# communication_module.net
KiCad netlist of a schematic drawn in EAGLE
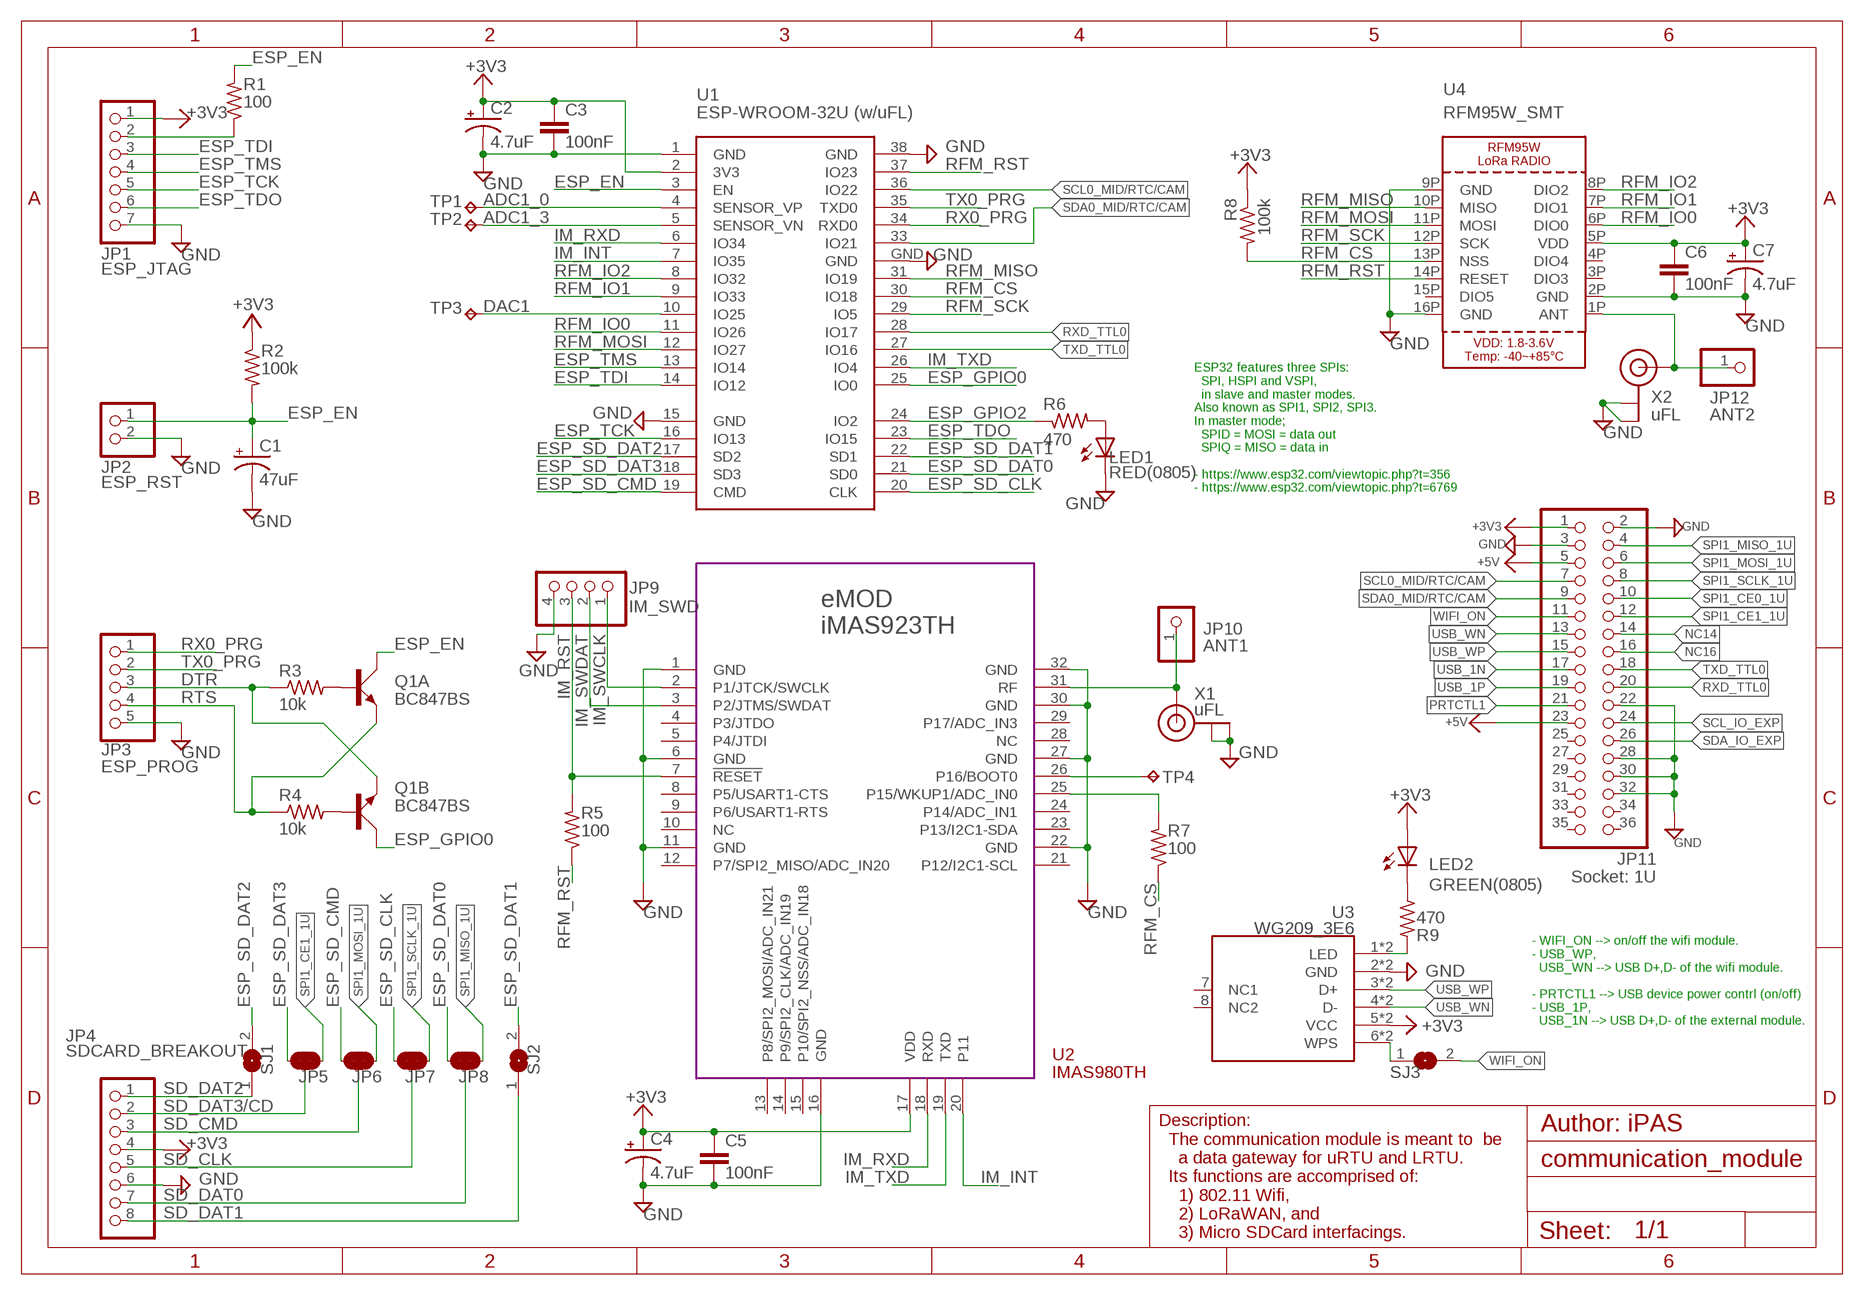
[diagram p0: schematic, sheet 1]

(export (version "E")
  (design (tool "Eeschema 10.0.6"))
  (components
    (comp (ref "C1")
      (value "47uF")
      (footprint "eagle-import:RCL_150CLZ-1014")
      (libsource (lib "eagle-import") (part "RCL_CPOL-US150CLZ-1014"))
    )
    (comp (ref "C2")
      (value "4.7uF")
      (footprint "eagle-import:RCL_150CLZ-1014")
      (libsource (lib "eagle-import") (part "RCL_CPOL-US150CLZ-1014"))
    )
    (comp (ref "C3")
      (value "100nF")
      (footprint "eagle-import:RCL_C1206")
      (libsource (lib "eagle-import") (part "RCL_C-EUC1206"))
    )
    (comp (ref "C4")
      (value "4.7uF")
      (footprint "eagle-import:RCL_150CLZ-1014")
      (libsource (lib "eagle-import") (part "RCL_CPOL-US150CLZ-1014"))
    )
    (comp (ref "C5")
      (value "100nF")
      (footprint "eagle-import:RCL_C1206")
      (libsource (lib "eagle-import") (part "RCL_C-EUC1206"))
    )
    (comp (ref "C6")
      (value "100nF")
      (footprint "eagle-import:RCL_C1206")
      (libsource (lib "eagle-import") (part "RCL_C-EUC1206"))
    )
    (comp (ref "C7")
      (value "4.7uF")
      (footprint "eagle-import:RCL_150CLZ-1014")
      (libsource (lib "eagle-import") (part "RCL_CPOL-US150CLZ-1014"))
    )
    (comp (ref "JP1")
      (value "ESP_JTAG")
      (footprint "eagle-import:1X07")
      (libsource (lib "eagle-import") (part "PINHD-1X7"))
    )
    (comp (ref "JP2")
      (value "ESP_RST")
      (footprint "eagle-import:1X02")
      (libsource (lib "eagle-import") (part "PINHD-1X2"))
    )
    (comp (ref "JP3")
      (value "ESP_PROG")
      (footprint "eagle-import:1X05")
      (libsource (lib "eagle-import") (part "PINHD-1X5"))
    )
    (comp (ref "JP4")
      (value "SDCARD_BREAKOUT")
      (footprint "eagle-import:1X08")
      (libsource (lib "eagle-import") (part "PINHD-1X8"))
    )
    (comp (ref "JP5")
      (value "JUMPER-SMT_3_NO_NO-SILK")
      (footprint "eagle-import:SMT-JUMPER_3_NO_NO-SILK")
      (libsource (lib "eagle-import") (part "JUMPER-SMT_3_NO_NO-SILK"))
    )
    (comp (ref "JP6")
      (value "JUMPER-SMT_3_NO_NO-SILK")
      (footprint "eagle-import:SMT-JUMPER_3_NO_NO-SILK")
      (libsource (lib "eagle-import") (part "JUMPER-SMT_3_NO_NO-SILK"))
    )
    (comp (ref "JP7")
      (value "JUMPER-SMT_3_NO_NO-SILK")
      (footprint "eagle-import:SMT-JUMPER_3_NO_NO-SILK")
      (libsource (lib "eagle-import") (part "JUMPER-SMT_3_NO_NO-SILK"))
    )
    (comp (ref "JP8")
      (value "JUMPER-SMT_3_NO_NO-SILK")
      (footprint "eagle-import:SMT-JUMPER_3_NO_NO-SILK")
      (libsource (lib "eagle-import") (part "JUMPER-SMT_3_NO_NO-SILK"))
    )
    (comp (ref "JP9")
      (value "IM_SWD")
      (footprint "eagle-import:1X04")
      (libsource (lib "eagle-import") (part "PINHD-1X4"))
    )
    (comp (ref "JP10")
      (value "ANT1")
      (footprint "eagle-import:1X01_ROUND")
      (libsource (lib "eagle-import") (part "HEADER-1X1ROUND"))
    )
    (comp (ref "JP11")
      (value "Socket: 1U")
      (footprint "eagle-import:2X18")
      (libsource (lib "eagle-import") (part "PINHD-2X18"))
    )
    (comp (ref "JP12")
      (value "ANT2")
      (footprint "eagle-import:1X01_ROUND")
      (libsource (lib "eagle-import") (part "HEADER-1X1ROUND"))
    )
    (comp (ref "LED1")
      (value "RED(0805)")
      (footprint "eagle-import:CHIP-LED0805")
      (libsource (lib "eagle-import") (part "LEDCHIP-LED0805"))
    )
    (comp (ref "LED2")
      (value "GREEN(0805)")
      (footprint "eagle-import:CHIP-LED0805")
      (libsource (lib "eagle-import") (part "LEDCHIP-LED0805"))
    )
    (comp (ref "Q1")
      (value "BC847BS")
      (footprint "eagle-import:SOT363_PHILIPS")
      (libsource (lib "eagle-import") (part "BC847BS"))
    )
    (comp (ref "R1")
      (value "100")
      (footprint "eagle-import:RCL_M0805")
      (libsource (lib "eagle-import") (part "RCL_R-USM0805"))
    )
    (comp (ref "R2")
      (value "100k")
      (footprint "eagle-import:RCL_M0805")
      (libsource (lib "eagle-import") (part "RCL_R-USM0805"))
    )
    (comp (ref "R3")
      (value "10k")
      (footprint "eagle-import:RCL_M0805")
      (libsource (lib "eagle-import") (part "RCL_R-USM0805"))
    )
    (comp (ref "R4")
      (value "10k")
      (footprint "eagle-import:RCL_M0805")
      (libsource (lib "eagle-import") (part "RCL_R-USM0805"))
    )
    (comp (ref "R5")
      (value "100")
      (footprint "eagle-import:RCL_M0805")
      (libsource (lib "eagle-import") (part "RCL_R-USM0805"))
    )
    (comp (ref "R6")
      (value "470")
      (footprint "eagle-import:RCL_M0805")
      (libsource (lib "eagle-import") (part "RCL_R-USM0805"))
    )
    (comp (ref "R7")
      (value "100")
      (footprint "eagle-import:RCL_M0805")
      (libsource (lib "eagle-import") (part "RCL_R-USM0805"))
    )
    (comp (ref "R8")
      (value "100k")
      (footprint "eagle-import:RCL_M0805")
      (libsource (lib "eagle-import") (part "RCL_R-USM0805"))
    )
    (comp (ref "R9")
      (value "470")
      (footprint "eagle-import:RCL_M0805")
      (libsource (lib "eagle-import") (part "RCL_R-USM0805"))
    )
    (comp (ref "SJ1")
      (value "SOLDERJUMPERREFLOW")
      (footprint "eagle-import:SOLDERJUMPER_REFLOW")
      (libsource (lib "eagle-import") (part "SOLDERJUMPERREFLOW"))
    )
    (comp (ref "SJ2")
      (value "SOLDERJUMPERREFLOW")
      (footprint "eagle-import:SOLDERJUMPER_REFLOW")
      (libsource (lib "eagle-import") (part "SOLDERJUMPERREFLOW"))
    )
    (comp (ref "SJ3")
      (value "SOLDERJUMPERREFLOW")
      (footprint "eagle-import:SOLDERJUMPER_REFLOW")
      (libsource (lib "eagle-import") (part "SOLDERJUMPERREFLOW"))
    )
    (comp (ref "TP1")
      (value "TPB1,27")
      (footprint "eagle-import:B1,27")
      (libsource (lib "eagle-import") (part "TPB1,27"))
    )
    (comp (ref "TP2")
      (value "TPB1,27")
      (footprint "eagle-import:B1,27")
      (libsource (lib "eagle-import") (part "TPB1,27"))
    )
    (comp (ref "TP3")
      (value "TPB1,27")
      (footprint "eagle-import:B1,27")
      (libsource (lib "eagle-import") (part "TPB1,27"))
    )
    (comp (ref "TP4")
      (value "TPB1,27")
      (footprint "eagle-import:B1,27")
      (libsource (lib "eagle-import") (part "TPB1,27"))
    )
    (comp (ref "U1")
      (value "ESP-WROOM-32U (w/uFL)")
      (footprint "eagle-import:ESP-WROOM-32")
      (libsource (lib "eagle-import") (part "ESP-WROOM-32"))
    )
    (comp (ref "U2")
      (value "IMAS980TH")
      (footprint "eagle-import:IMAS923TH")
      (libsource (lib "eagle-import") (part "IMAS980TH"))
    )
    (comp (ref "U3")
      (value "WG209_3E6")
      (footprint "eagle-import:WG209")
      (libsource (lib "eagle-import") (part "WG209"))
    )
    (comp (ref "U4")
      (value "RFM95W_SMT")
      (footprint "eagle-import:RFMHCW_SMT")
      (libsource (lib "eagle-import") (part "RFM95W_SMT"))
    )
    (comp (ref "X1")
      (value "uFL")
      (footprint "eagle-import:U.FL")
      (libsource (lib "eagle-import") (part "ANTENNA_U.FL"))
    )
    (comp (ref "X2")
      (value "uFL")
      (footprint "eagle-import:U.FL")
      (libsource (lib "eagle-import") (part "ANTENNA_U.FL"))
    )
  )
  (nets
    (net (code "1") (name "+3V3") (class "Default")
      (node (ref "C2") (pin "+") (pinfunction "+_+") (pintype "passive"))
      (node (ref "C3") (pin "1") (pinfunction "1_1") (pintype "passive"))
      (node (ref "C4") (pin "+") (pinfunction "+_+") (pintype "passive"))
      (node (ref "C5") (pin "1") (pinfunction "1_1") (pintype "passive"))
      (node (ref "C6") (pin "1") (pinfunction "1_1") (pintype "passive"))
      (node (ref "C7") (pin "+") (pinfunction "+_+") (pintype "passive"))
      (node (ref "JP1") (pin "1") (pinfunction "1_1") (pintype "passive"))
      (node (ref "JP11") (pin "1") (pinfunction "1_1") (pintype "passive"))
      (node (ref "JP4") (pin "4") (pinfunction "4_4") (pintype "passive"))
      (node (ref "LED2") (pin "A") (pinfunction "A_A") (pintype "passive"))
      (node (ref "R2") (pin "1") (pinfunction "1_1") (pintype "passive"))
      (node (ref "R8") (pin "1") (pinfunction "1_1") (pintype "passive"))
      (node (ref "U1") (pin "2") (pinfunction "3V3_2") (pintype "power_in"))
      (node (ref "U2") (pin "17") (pinfunction "VDD_17") (pintype "power_in"))
      (node (ref "U3") (pin "5") (pinfunction "VCC_5") (pintype "power_in"))
      (node (ref "U3") (pin "5P") (pinfunction "VCC_5P") (pintype "power_in"))
      (node (ref "U4") (pin "5P") (pinfunction "VDD_5P") (pintype "power_in"))
    )
    (net (code "2") (name "+5V") (class "Default")
      (node (ref "JP11") (pin "23") (pinfunction "23_23") (pintype "passive"))
      (node (ref "JP11") (pin "5") (pinfunction "5_5") (pintype "passive"))
    )
    (net (code "3") (name "/ADC1_0") (class "Default")
      (node (ref "TP1") (pin "TP") (pinfunction "TP_TP") (pintype "input"))
      (node (ref "U1") (pin "4") (pinfunction "SENSOR_VP_4") (pintype "bidirectional"))
    )
    (net (code "4") (name "/ADC1_3") (class "Default")
      (node (ref "TP2") (pin "TP") (pinfunction "TP_TP") (pintype "input"))
      (node (ref "U1") (pin "5") (pinfunction "SENSOR_VN_5") (pintype "bidirectional"))
    )
    (net (code "5") (name "/DAC1") (class "Default")
      (node (ref "TP3") (pin "TP") (pinfunction "TP_TP") (pintype "input"))
      (node (ref "U1") (pin "10") (pinfunction "IO25_10") (pintype "bidirectional"))
    )
    (net (code "6") (name "/DTR") (class "Default")
      (node (ref "JP3") (pin "3") (pinfunction "3_3") (pintype "passive"))
      (node (ref "Q1") (pin "4") (pinfunction "E_4") (pintype "passive"))
      (node (ref "R3") (pin "1") (pinfunction "1_1") (pintype "passive"))
    )
    (net (code "7") (name "/ESP_EN") (class "Default")
      (node (ref "C1") (pin "+") (pinfunction "+_+") (pintype "passive"))
      (node (ref "JP2") (pin "1") (pinfunction "1_1") (pintype "passive"))
      (node (ref "Q1") (pin "6") (pinfunction "C_6") (pintype "passive"))
      (node (ref "R1") (pin "2") (pinfunction "2_2") (pintype "passive"))
      (node (ref "R2") (pin "2") (pinfunction "2_2") (pintype "passive"))
      (node (ref "U1") (pin "3") (pinfunction "EN_3") (pintype "input"))
    )
    (net (code "8") (name "/ESP_GPIO0") (class "Default")
      (node (ref "Q1") (pin "3") (pinfunction "C_3") (pintype "passive"))
      (node (ref "U1") (pin "25") (pinfunction "IO0_25") (pintype "bidirectional"))
    )
    (net (code "9") (name "/ESP_GPIO2") (class "Default")
      (node (ref "R6") (pin "1") (pinfunction "1_1") (pintype "passive"))
      (node (ref "U1") (pin "24") (pinfunction "IO2_24") (pintype "bidirectional"))
    )
    (net (code "10") (name "/ESP_SD_CLK") (class "Default")
      (node (ref "JP7") (pin "1") (pinfunction "1_1") (pintype "passive"))
      (node (ref "U1") (pin "20") (pinfunction "CLK_20") (pintype "bidirectional"))
    )
    (net (code "11") (name "/ESP_SD_CMD") (class "Default")
      (node (ref "JP6") (pin "1") (pinfunction "1_1") (pintype "passive"))
      (node (ref "U1") (pin "19") (pinfunction "CMD_19") (pintype "bidirectional"))
    )
    (net (code "12") (name "/ESP_SD_DAT0") (class "Default")
      (node (ref "JP8") (pin "1") (pinfunction "1_1") (pintype "passive"))
      (node (ref "U1") (pin "21") (pinfunction "SD0_21") (pintype "bidirectional"))
    )
    (net (code "13") (name "/ESP_SD_DAT1") (class "Default")
      (node (ref "SJ2") (pin "2") (pinfunction "2_2") (pintype "passive"))
      (node (ref "U1") (pin "22") (pinfunction "SD1_22") (pintype "bidirectional"))
    )
    (net (code "14") (name "/ESP_SD_DAT2") (class "Default")
      (node (ref "SJ1") (pin "2") (pinfunction "2_2") (pintype "passive"))
      (node (ref "U1") (pin "17") (pinfunction "SD2_17") (pintype "bidirectional"))
    )
    (net (code "15") (name "/ESP_SD_DAT3") (class "Default")
      (node (ref "JP5") (pin "1") (pinfunction "1_1") (pintype "passive"))
      (node (ref "U1") (pin "18") (pinfunction "SD3_18") (pintype "bidirectional"))
    )
    (net (code "16") (name "/ESP_TCK") (class "Default")
      (node (ref "JP1") (pin "5") (pinfunction "5_5") (pintype "passive"))
      (node (ref "U1") (pin "16") (pinfunction "IO13_16") (pintype "bidirectional"))
    )
    (net (code "17") (name "/ESP_TDI") (class "Default")
      (node (ref "JP1") (pin "3") (pinfunction "3_3") (pintype "passive"))
      (node (ref "U1") (pin "14") (pinfunction "IO12_14") (pintype "bidirectional"))
    )
    (net (code "18") (name "/ESP_TDO") (class "Default")
      (node (ref "JP1") (pin "6") (pinfunction "6_6") (pintype "passive"))
      (node (ref "U1") (pin "23") (pinfunction "IO15_23") (pintype "bidirectional"))
    )
    (net (code "19") (name "/ESP_TMS") (class "Default")
      (node (ref "JP1") (pin "4") (pinfunction "4_4") (pintype "passive"))
      (node (ref "U1") (pin "13") (pinfunction "IO14_13") (pintype "bidirectional"))
    )
    (net (code "20") (name "/IM_INT") (class "Default")
      (node (ref "U1") (pin "7") (pinfunction "IO35_7") (pintype "bidirectional"))
      (node (ref "U2") (pin "20") (pinfunction "P11_20") (pintype "bidirectional"))
    )
    (net (code "21") (name "/IM_RST") (class "Default")
      (node (ref "JP9") (pin "3") (pinfunction "3_3") (pintype "passive"))
      (node (ref "R5") (pin "2") (pinfunction "2_2") (pintype "passive"))
      (node (ref "U2") (pin "7") (pinfunction "~{RESET}_7") (pintype "passive"))
    )
    (net (code "22") (name "/IM_RXD") (class "Default")
      (node (ref "U1") (pin "6") (pinfunction "IO34_6") (pintype "bidirectional"))
      (node (ref "U2") (pin "18") (pinfunction "RXD_18") (pintype "bidirectional"))
    )
    (net (code "23") (name "/IM_SWCLK") (class "Default")
      (node (ref "JP9") (pin "1") (pinfunction "1_1") (pintype "passive"))
      (node (ref "U2") (pin "2") (pinfunction "P1/JTCK/SWCLK_2") (pintype "bidirectional"))
    )
    (net (code "24") (name "/IM_SWDAT") (class "Default")
      (node (ref "JP9") (pin "2") (pinfunction "2_2") (pintype "passive"))
      (node (ref "U2") (pin "3") (pinfunction "P2/JTMS/SWDAT_3") (pintype "bidirectional"))
    )
    (net (code "25") (name "/IM_TXD") (class "Default")
      (node (ref "U1") (pin "26") (pinfunction "IO4_26") (pintype "bidirectional"))
      (node (ref "U2") (pin "19") (pinfunction "TXD_19") (pintype "bidirectional"))
    )
    (net (code "26") (name "/RFM_CS") (class "Default")
      (node (ref "R7") (pin "1") (pinfunction "1_1") (pintype "passive"))
      (node (ref "R8") (pin "2") (pinfunction "2_2") (pintype "passive"))
      (node (ref "U1") (pin "30") (pinfunction "IO18_30") (pintype "bidirectional"))
      (node (ref "U4") (pin "13P") (pinfunction "NSS_13P") (pintype "input"))
    )
    (net (code "27") (name "/RFM_IO0") (class "Default")
      (node (ref "U1") (pin "11") (pinfunction "IO26_11") (pintype "bidirectional"))
      (node (ref "U4") (pin "6P") (pinfunction "DIO0_6P") (pintype "bidirectional"))
    )
    (net (code "28") (name "/RFM_IO1") (class "Default")
      (node (ref "U1") (pin "9") (pinfunction "IO33_9") (pintype "bidirectional"))
      (node (ref "U4") (pin "7P") (pinfunction "DIO1_7P") (pintype "bidirectional"))
    )
    (net (code "29") (name "/RFM_IO2") (class "Default")
      (node (ref "U1") (pin "8") (pinfunction "IO32_8") (pintype "bidirectional"))
      (node (ref "U4") (pin "8P") (pinfunction "DIO2_8P") (pintype "bidirectional"))
    )
    (net (code "30") (name "/RFM_MISO") (class "Default")
      (node (ref "U1") (pin "31") (pinfunction "IO19_31") (pintype "bidirectional"))
      (node (ref "U4") (pin "10P") (pinfunction "MISO_10P") (pintype "output"))
    )
    (net (code "31") (name "/RFM_MOSI") (class "Default")
      (node (ref "U1") (pin "12") (pinfunction "IO27_12") (pintype "bidirectional"))
      (node (ref "U4") (pin "11P") (pinfunction "MOSI_11P") (pintype "input"))
    )
    (net (code "32") (name "/RFM_RST") (class "Default")
      (node (ref "R5") (pin "1") (pinfunction "1_1") (pintype "passive"))
      (node (ref "U1") (pin "37") (pinfunction "IO23_37") (pintype "bidirectional"))
      (node (ref "U4") (pin "14P") (pinfunction "RESET_14P") (pintype "input"))
    )
    (net (code "33") (name "/RFM_SCK") (class "Default")
      (node (ref "U1") (pin "29") (pinfunction "IO5_29") (pintype "bidirectional"))
      (node (ref "U4") (pin "12P") (pinfunction "SCK_12P") (pintype "input"))
    )
    (net (code "34") (name "/RTS") (class "Default")
      (node (ref "JP3") (pin "4") (pinfunction "4_4") (pintype "passive"))
      (node (ref "Q1") (pin "1") (pinfunction "E_1") (pintype "passive"))
      (node (ref "R4") (pin "1") (pinfunction "1_1") (pintype "passive"))
    )
    (net (code "35") (name "/RX0_PRG") (class "Default")
      (node (ref "JP3") (pin "1") (pinfunction "1_1") (pintype "passive"))
      (node (ref "U1") (pin "34") (pinfunction "RXD0_34") (pintype "bidirectional"))
    )
    (net (code "36") (name "/SD_CLK") (class "Default")
      (node (ref "JP4") (pin "5") (pinfunction "5_5") (pintype "passive"))
      (node (ref "JP7") (pin "2") (pinfunction "2_2") (pintype "passive"))
    )
    (net (code "37") (name "/SD_CMD") (class "Default")
      (node (ref "JP4") (pin "3") (pinfunction "3_3") (pintype "passive"))
      (node (ref "JP6") (pin "2") (pinfunction "2_2") (pintype "passive"))
    )
    (net (code "38") (name "/SD_DAT0") (class "Default")
      (node (ref "JP4") (pin "7") (pinfunction "7_7") (pintype "passive"))
      (node (ref "JP8") (pin "2") (pinfunction "2_2") (pintype "passive"))
    )
    (net (code "39") (name "/SD_DAT1") (class "Default")
      (node (ref "JP4") (pin "8") (pinfunction "8_8") (pintype "passive"))
      (node (ref "SJ2") (pin "1") (pinfunction "1_1") (pintype "passive"))
    )
    (net (code "40") (name "/SD_DAT2") (class "Default")
      (node (ref "JP4") (pin "1") (pinfunction "1_1") (pintype "passive"))
      (node (ref "SJ1") (pin "1") (pinfunction "1_1") (pintype "passive"))
    )
    (net (code "41") (name "/SD_DAT3{slash}CD") (class "Default")
      (node (ref "JP4") (pin "2") (pinfunction "2_2") (pintype "passive"))
      (node (ref "JP5") (pin "2") (pinfunction "2_2") (pintype "passive"))
    )
    (net (code "42") (name "/TX0_PRG") (class "Default")
      (node (ref "JP3") (pin "2") (pinfunction "2_2") (pintype "passive"))
      (node (ref "U1") (pin "35") (pinfunction "TXD0_35") (pintype "bidirectional"))
    )
    (net (code "43") (name "GND") (class "Default")
      (node (ref "C1") (pin "-") (pinfunction "-_-") (pintype "passive"))
      (node (ref "C2") (pin "-") (pinfunction "-_-") (pintype "passive"))
      (node (ref "C3") (pin "2") (pinfunction "2_2") (pintype "passive"))
      (node (ref "C4") (pin "-") (pinfunction "-_-") (pintype "passive"))
      (node (ref "C5") (pin "2") (pinfunction "2_2") (pintype "passive"))
      (node (ref "C6") (pin "2") (pinfunction "2_2") (pintype "passive"))
      (node (ref "C7") (pin "-") (pinfunction "-_-") (pintype "passive"))
      (node (ref "JP1") (pin "7") (pinfunction "7_7") (pintype "passive"))
      (node (ref "JP11") (pin "2") (pinfunction "2_2") (pintype "passive"))
      (node (ref "JP11") (pin "22") (pinfunction "22_22") (pintype "passive"))
      (node (ref "JP11") (pin "28") (pinfunction "28_28") (pintype "passive"))
      (node (ref "JP11") (pin "3") (pinfunction "3_3") (pintype "passive"))
      (node (ref "JP11") (pin "30") (pinfunction "30_30") (pintype "passive"))
      (node (ref "JP11") (pin "32") (pinfunction "32_32") (pintype "passive"))
      (node (ref "JP2") (pin "2") (pinfunction "2_2") (pintype "passive"))
      (node (ref "JP3") (pin "5") (pinfunction "5_5") (pintype "passive"))
      (node (ref "JP4") (pin "6") (pinfunction "6_6") (pintype "passive"))
      (node (ref "JP9") (pin "4") (pinfunction "4_4") (pintype "passive"))
      (node (ref "LED1") (pin "C") (pinfunction "C_C") (pintype "passive"))
      (node (ref "U1") (pin "1") (pinfunction "GND_1") (pintype "power_in"))
      (node (ref "U1") (pin "15") (pinfunction "GND_15") (pintype "power_in"))
      (node (ref "U1") (pin "38") (pinfunction "GND_38") (pintype "power_in"))
      (node (ref "U1") (pin "GND") (pinfunction "GND_GND") (pintype "power_in"))
      (node (ref "U2") (pin "1") (pinfunction "GND_1") (pintype "power_in"))
      (node (ref "U2") (pin "11") (pinfunction "GND_11") (pintype "power_in"))
      (node (ref "U2") (pin "16") (pinfunction "GND_16") (pintype "power_in"))
      (node (ref "U2") (pin "22") (pinfunction "GND_22") (pintype "power_in"))
      (node (ref "U2") (pin "27") (pinfunction "GND_27") (pintype "power_in"))
      (node (ref "U2") (pin "30") (pinfunction "GND_30") (pintype "power_in"))
      (node (ref "U2") (pin "32") (pinfunction "GND_32") (pintype "power_in"))
      (node (ref "U2") (pin "6") (pinfunction "GND_6") (pintype "power_in"))
      (node (ref "U3") (pin "2") (pinfunction "GND_2") (pintype "power_in"))
      (node (ref "U3") (pin "2P") (pinfunction "GND_2P") (pintype "power_in"))
      (node (ref "U4") (pin "16P") (pinfunction "GND_16P") (pintype "power_in"))
      (node (ref "U4") (pin "2P") (pinfunction "GND_2P") (pintype "power_in"))
      (node (ref "U4") (pin "9P") (pinfunction "GND_9P") (pintype "power_in"))
      (node (ref "X1") (pin "1") (pinfunction "GND_1") (pintype "passive"))
      (node (ref "X1") (pin "2") (pinfunction "GND_2") (pintype "passive"))
      (node (ref "X2") (pin "1") (pinfunction "GND_1") (pintype "passive"))
      (node (ref "X2") (pin "2") (pinfunction "GND_2") (pintype "passive"))
    )
    (net (code "44") (name "NC14") (class "Default")
      (node (ref "JP11") (pin "14") (pinfunction "14_14") (pintype "passive"))
    )
    (net (code "45") (name "NC16") (class "Default")
      (node (ref "JP11") (pin "16") (pinfunction "16_16") (pintype "passive"))
    )
    (net (code "46") (name "Net-(JP1-Pad2)") (class "Default")
      (node (ref "JP1") (pin "2") (pinfunction "2_2") (pintype "passive"))
      (node (ref "R1") (pin "1") (pinfunction "1_1") (pintype "passive"))
    )
    (net (code "47") (name "Net-(LED1-PadA)") (class "Default")
      (node (ref "LED1") (pin "A") (pinfunction "A_A") (pintype "passive"))
      (node (ref "R6") (pin "2") (pinfunction "2_2") (pintype "passive"))
    )
    (net (code "48") (name "Net-(LED2-PadC)") (class "Default")
      (node (ref "LED2") (pin "C") (pinfunction "C_C") (pintype "passive"))
      (node (ref "R9") (pin "1") (pinfunction "1_1") (pintype "passive"))
    )
    (net (code "49") (name "Net-(Q1A-B)") (class "Default")
      (node (ref "Q1") (pin "2") (pinfunction "B_2") (pintype "passive"))
      (node (ref "R3") (pin "2") (pinfunction "2_2") (pintype "passive"))
    )
    (net (code "50") (name "Net-(Q1B-B)") (class "Default")
      (node (ref "Q1") (pin "5") (pinfunction "B_5") (pintype "passive"))
      (node (ref "R4") (pin "2") (pinfunction "2_2") (pintype "passive"))
    )
    (net (code "51") (name "Net-(R9-Pad2)") (class "Default")
      (node (ref "R9") (pin "2") (pinfunction "2_2") (pintype "passive"))
      (node (ref "U3") (pin "1") (pinfunction "LED_1") (pintype "bidirectional"))
      (node (ref "U3") (pin "1P") (pinfunction "LED_1P") (pintype "bidirectional"))
    )
    (net (code "52") (name "Net-(SJ3-Pad1)") (class "Default")
      (node (ref "SJ3") (pin "1") (pinfunction "1_1") (pintype "passive"))
      (node (ref "U3") (pin "6") (pinfunction "WPS_6") (pintype "bidirectional"))
      (node (ref "U3") (pin "6P") (pinfunction "WPS_6P") (pintype "bidirectional"))
    )
    (net (code "53") (name "Net-(U2-P15{slash}WKUP1{slash}ADC_IN0)") (class "Default")
      (node (ref "R7") (pin "2") (pinfunction "2_2") (pintype "passive"))
      (node (ref "U2") (pin "25") (pinfunction "P15/WKUP1/ADC_IN0_25") (pintype "bidirectional"))
    )
    (net (code "54") (name "Net-(U2-P16{slash}BOOT0)") (class "Default")
      (node (ref "TP4") (pin "TP") (pinfunction "TP_TP") (pintype "input"))
      (node (ref "U2") (pin "26") (pinfunction "P16/BOOT0_26") (pintype "passive"))
    )
    (net (code "55") (name "Net-(U2-RF)") (class "Default")
      (node (ref "JP10") (pin "1") (pinfunction "1_1") (pintype "passive"))
      (node (ref "U2") (pin "31") (pinfunction "RF_31") (pintype "bidirectional"))
      (node (ref "X1") (pin "3") (pinfunction "SIGNAL_3") (pintype "passive"))
    )
    (net (code "56") (name "Net-(U4-ANT)") (class "Default")
      (node (ref "JP12") (pin "1") (pinfunction "1_1") (pintype "passive"))
      (node (ref "U4") (pin "1P") (pinfunction "ANT_1P") (pintype "bidirectional"))
      (node (ref "X2") (pin "3") (pinfunction "SIGNAL_3") (pintype "passive"))
    )
    (net (code "57") (name "PRTCTL1") (class "Default")
      (node (ref "JP11") (pin "21") (pinfunction "21_21") (pintype "passive"))
    )
    (net (code "58") (name "RXD_TTL0") (class "Default")
      (node (ref "JP11") (pin "20") (pinfunction "20_20") (pintype "passive"))
      (node (ref "U1") (pin "28") (pinfunction "IO17_28") (pintype "bidirectional"))
    )
    (net (code "59") (name "SCL0_MID{slash}RTC{slash}CAM") (class "Default")
      (node (ref "JP11") (pin "7") (pinfunction "7_7") (pintype "passive"))
      (node (ref "U1") (pin "36") (pinfunction "IO22_36") (pintype "bidirectional"))
    )
    (net (code "60") (name "SCL_IO_EXP") (class "Default")
      (node (ref "JP11") (pin "24") (pinfunction "24_24") (pintype "passive"))
    )
    (net (code "61") (name "SDA0_MID{slash}RTC{slash}CAM") (class "Default")
      (node (ref "JP11") (pin "9") (pinfunction "9_9") (pintype "passive"))
      (node (ref "U1") (pin "33") (pinfunction "IO21_33") (pintype "bidirectional"))
    )
    (net (code "62") (name "SDA_IO_EXP") (class "Default")
      (node (ref "JP11") (pin "26") (pinfunction "26_26") (pintype "passive"))
    )
    (net (code "63") (name "SPI1_CE0_1U") (class "Default")
      (node (ref "JP11") (pin "10") (pinfunction "10_10") (pintype "passive"))
    )
    (net (code "64") (name "SPI1_CE1_1U") (class "Default")
      (node (ref "JP11") (pin "12") (pinfunction "12_12") (pintype "passive"))
      (node (ref "JP5") (pin "3") (pinfunction "3_3") (pintype "passive"))
    )
    (net (code "65") (name "SPI1_MISO_1U") (class "Default")
      (node (ref "JP11") (pin "4") (pinfunction "4_4") (pintype "passive"))
      (node (ref "JP8") (pin "3") (pinfunction "3_3") (pintype "passive"))
    )
    (net (code "66") (name "SPI1_MOSI_1U") (class "Default")
      (node (ref "JP11") (pin "6") (pinfunction "6_6") (pintype "passive"))
      (node (ref "JP6") (pin "3") (pinfunction "3_3") (pintype "passive"))
    )
    (net (code "67") (name "SPI1_SCLK_1U") (class "Default")
      (node (ref "JP11") (pin "8") (pinfunction "8_8") (pintype "passive"))
      (node (ref "JP7") (pin "3") (pinfunction "3_3") (pintype "passive"))
    )
    (net (code "68") (name "TXD_TTL0") (class "Default")
      (node (ref "JP11") (pin "18") (pinfunction "18_18") (pintype "passive"))
      (node (ref "U1") (pin "27") (pinfunction "IO16_27") (pintype "bidirectional"))
    )
    (net (code "69") (name "USB_1N") (class "Default")
      (node (ref "JP11") (pin "17") (pinfunction "17_17") (pintype "passive"))
    )
    (net (code "70") (name "USB_1P") (class "Default")
      (node (ref "JP11") (pin "19") (pinfunction "19_19") (pintype "passive"))
    )
    (net (code "71") (name "USB_WN") (class "Default")
      (node (ref "JP11") (pin "13") (pinfunction "13_13") (pintype "passive"))
      (node (ref "U3") (pin "4") (pinfunction "D-_4") (pintype "bidirectional"))
      (node (ref "U3") (pin "4P") (pinfunction "D-_4P") (pintype "bidirectional"))
    )
    (net (code "72") (name "USB_WP") (class "Default")
      (node (ref "JP11") (pin "15") (pinfunction "15_15") (pintype "passive"))
      (node (ref "U3") (pin "3") (pinfunction "D+_3") (pintype "bidirectional"))
      (node (ref "U3") (pin "3P") (pinfunction "D+_3P") (pintype "bidirectional"))
    )
    (net (code "73") (name "WIFI_ON") (class "Default")
      (node (ref "JP11") (pin "11") (pinfunction "11_11") (pintype "passive"))
      (node (ref "SJ3") (pin "2") (pinfunction "2_2") (pintype "passive"))
    )
    (net (code "74") (name "unconnected-(JP11-Pad25)") (class "Default")
      (node (ref "JP11") (pin "25") (pinfunction "25_25") (pintype "passive"))
    )
    (net (code "75") (name "unconnected-(JP11-Pad27)") (class "Default")
      (node (ref "JP11") (pin "27") (pinfunction "27_27") (pintype "passive"))
    )
    (net (code "76") (name "unconnected-(JP11-Pad29)") (class "Default")
      (node (ref "JP11") (pin "29") (pinfunction "29_29") (pintype "passive"))
    )
    (net (code "77") (name "unconnected-(JP11-Pad31)") (class "Default")
      (node (ref "JP11") (pin "31") (pinfunction "31_31") (pintype "passive"))
    )
    (net (code "78") (name "unconnected-(JP11-Pad33)") (class "Default")
      (node (ref "JP11") (pin "33") (pinfunction "33_33") (pintype "passive"))
    )
    (net (code "79") (name "unconnected-(JP11-Pad34)") (class "Default")
      (node (ref "JP11") (pin "34") (pinfunction "34_34") (pintype "passive"))
    )
    (net (code "80") (name "unconnected-(JP11-Pad35)") (class "Default")
      (node (ref "JP11") (pin "35") (pinfunction "35_35") (pintype "passive"))
    )
    (net (code "81") (name "unconnected-(JP11-Pad36)") (class "Default")
      (node (ref "JP11") (pin "36") (pinfunction "36_36") (pintype "passive"))
    )
    (net (code "82") (name "unconnected-(U2-NC-Pad10)") (class "Default")
      (node (ref "U2") (pin "10") (pinfunction "NC_10") (pintype "no_connect"))
    )
    (net (code "83") (name "unconnected-(U2-NC-Pad28)") (class "Default")
      (node (ref "U2") (pin "28") (pinfunction "NC_28") (pintype "no_connect"))
    )
    (net (code "84") (name "unconnected-(U2-P3{slash}JTDO-Pad4)") (class "Default")
      (node (ref "U2") (pin "4") (pinfunction "P3/JTDO_4") (pintype "bidirectional"))
    )
    (net (code "85") (name "unconnected-(U2-P4{slash}JTDI-Pad5)") (class "Default")
      (node (ref "U2") (pin "5") (pinfunction "P4/JTDI_5") (pintype "bidirectional"))
    )
    (net (code "86") (name "unconnected-(U2-P5{slash}USART1-CTS-Pad8)") (class "Default")
      (node (ref "U2") (pin "8") (pinfunction "P5/USART1-CTS_8") (pintype "bidirectional"))
    )
    (net (code "87") (name "unconnected-(U2-P6{slash}USART1-RTS-Pad9)") (class "Default")
      (node (ref "U2") (pin "9") (pinfunction "P6/USART1-RTS_9") (pintype "bidirectional"))
    )
    (net (code "88") (name "unconnected-(U2-P7{slash}SPI2_MISO{slash}ADC_IN20-Pad12)") (class "Default")
      (node (ref "U2") (pin "12") (pinfunction "P7/SPI2_MISO/ADC_IN20_12") (pintype "bidirectional"))
    )
    (net (code "89") (name "unconnected-(U2-P8{slash}SPI2_MOSI{slash}ADC_IN21-Pad13)") (class "Default")
      (node (ref "U2") (pin "13") (pinfunction "P8/SPI2_MOSI/ADC_IN21_13") (pintype "bidirectional"))
    )
    (net (code "90") (name "unconnected-(U2-P9{slash}SPI2_CLK{slash}ADC_IN19-Pad14)") (class "Default")
      (node (ref "U2") (pin "14") (pinfunction "P9/SPI2_CLK/ADC_IN19_14") (pintype "bidirectional"))
    )
    (net (code "91") (name "unconnected-(U2-P10{slash}SPI2_NSS{slash}ADC_IN18-Pad15)") (class "Default")
      (node (ref "U2") (pin "15") (pinfunction "P10/SPI2_NSS/ADC_IN18_15") (pintype "bidirectional"))
    )
    (net (code "92") (name "unconnected-(U2-P12{slash}I2C1-SCL-Pad21)") (class "Default")
      (node (ref "U2") (pin "21") (pinfunction "P12/I2C1-SCL_21") (pintype "bidirectional"))
    )
    (net (code "93") (name "unconnected-(U2-P13{slash}I2C1-SDA-Pad23)") (class "Default")
      (node (ref "U2") (pin "23") (pinfunction "P13/I2C1-SDA_23") (pintype "bidirectional"))
    )
    (net (code "94") (name "unconnected-(U2-P14{slash}ADC_IN1-Pad24)") (class "Default")
      (node (ref "U2") (pin "24") (pinfunction "P14/ADC_IN1_24") (pintype "bidirectional"))
    )
    (net (code "95") (name "unconnected-(U2-P17{slash}ADC_IN3-Pad29)") (class "Default")
      (node (ref "U2") (pin "29") (pinfunction "P17/ADC_IN3_29") (pintype "bidirectional"))
    )
    (net (code "96") (name "unconnected-(U3-NC1-Pad7)") (class "Default")
      (node (ref "U3") (pin "7") (pinfunction "NC1_7") (pintype "no_connect"))
    )
    (net (code "97") (name "unconnected-(U3-NC2-Pad8)") (class "Default")
      (node (ref "U3") (pin "8") (pinfunction "NC2_8") (pintype "no_connect"))
    )
    (net (code "98") (name "unconnected-(U4-DIO3-Pad3P)") (class "Default")
      (node (ref "U4") (pin "3P") (pinfunction "DIO3_3P") (pintype "bidirectional"))
    )
    (net (code "99") (name "unconnected-(U4-DIO4-Pad4P)") (class "Default")
      (node (ref "U4") (pin "4P") (pinfunction "DIO4_4P") (pintype "bidirectional"))
    )
    (net (code "100") (name "unconnected-(U4-DIO5-Pad15P)") (class "Default")
      (node (ref "U4") (pin "15P") (pinfunction "DIO5_15P") (pintype "bidirectional"))
    )
  )
)
